# MCU.net
KiCad netlist of a schematic drawn in Altium Designer
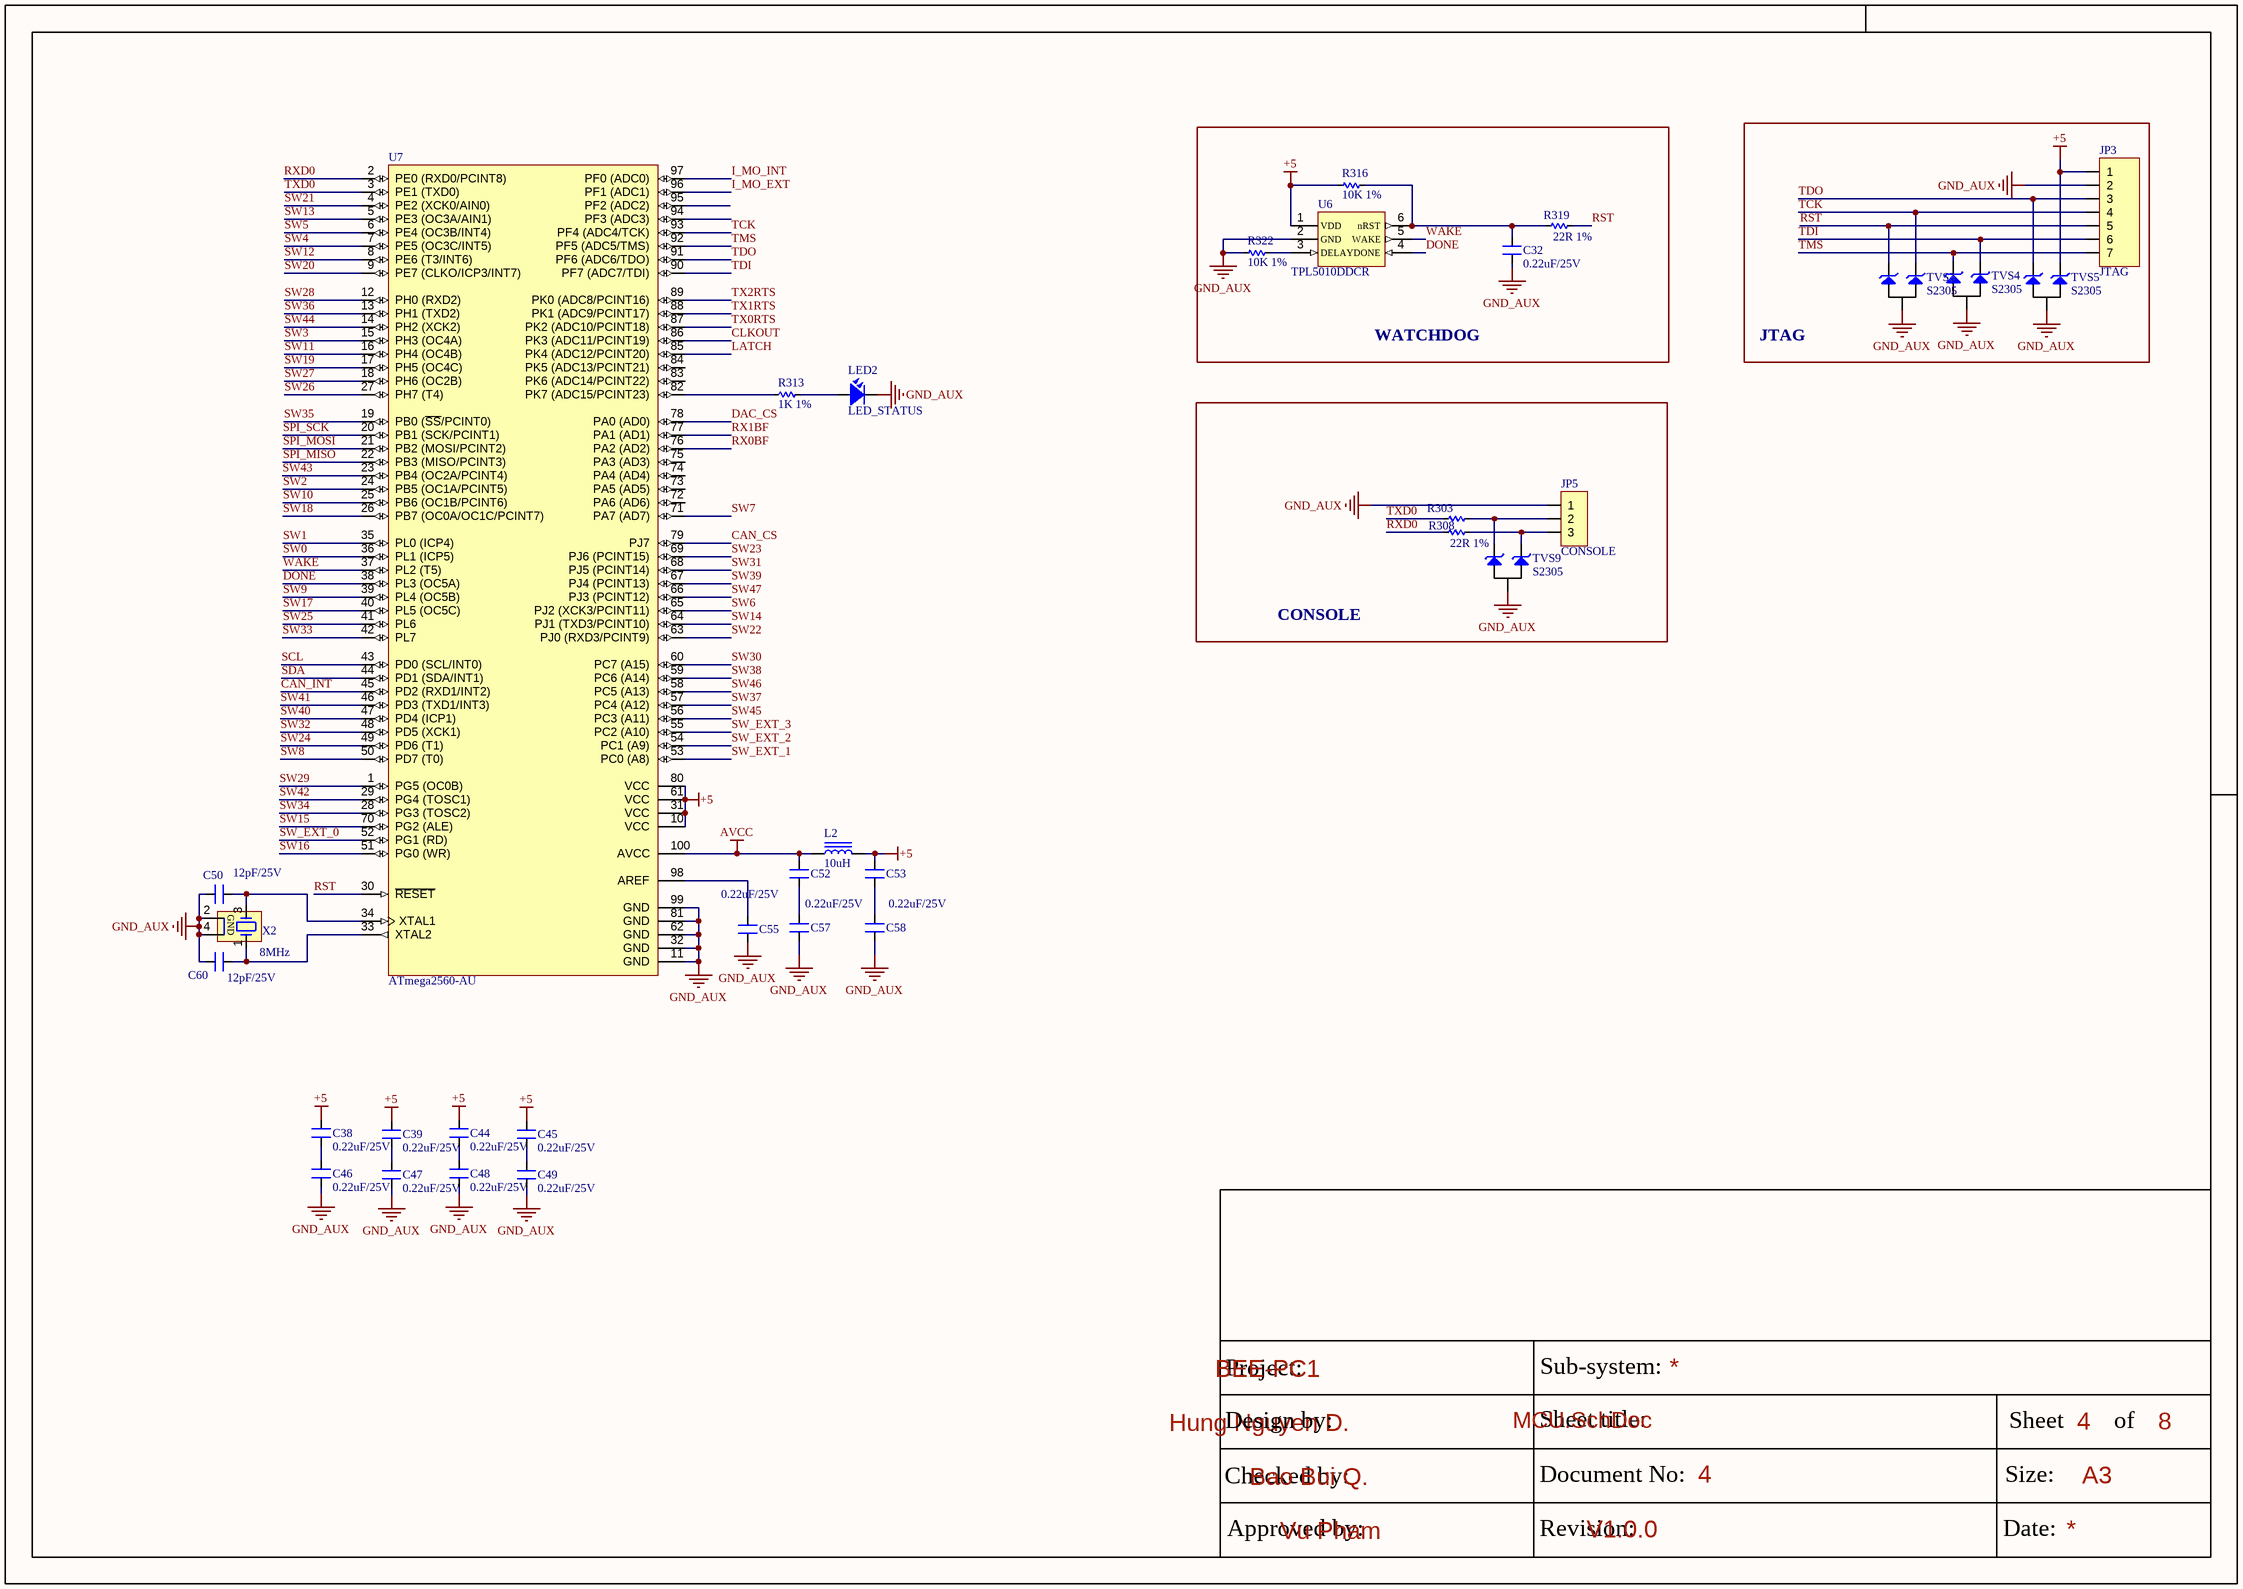
[diagram p0: MCU.SchDoc]

(export (version "E")
  (design (tool "Eeschema 10.0.6"))
  (components
    (comp (ref "C32")
      (value "0.22uF/25V")
      (footprint "SM-0603")
      (description "0603")
      (libsource (lib "Capacitors") (part "CM"))
    )
    (comp (ref "C38")
      (value "0.22uF/25V")
      (footprint "SM-0603")
      (description "0603")
      (libsource (lib "Capacitors") (part "CM"))
    )
    (comp (ref "C39")
      (value "0.22uF/25V")
      (footprint "SM-0603")
      (description "0603")
      (libsource (lib "Capacitors") (part "CM"))
    )
    (comp (ref "C44")
      (value "0.22uF/25V")
      (footprint "SM-0603")
      (description "0603")
      (libsource (lib "Capacitors") (part "CM"))
    )
    (comp (ref "C45")
      (value "0.22uF/25V")
      (footprint "SM-0603")
      (description "0603")
      (libsource (lib "Capacitors") (part "CM"))
    )
    (comp (ref "C46")
      (value "0.22uF/25V")
      (footprint "SM-0603")
      (description "0603")
      (libsource (lib "Capacitors") (part "CM"))
    )
    (comp (ref "C47")
      (value "0.22uF/25V")
      (footprint "SM-0603")
      (description "0603")
      (libsource (lib "Capacitors") (part "CM"))
    )
    (comp (ref "C48")
      (value "0.22uF/25V")
      (footprint "SM-0603")
      (description "0603")
      (libsource (lib "Capacitors") (part "CM"))
    )
    (comp (ref "C49")
      (value "0.22uF/25V")
      (footprint "SM-0603")
      (description "0603")
      (libsource (lib "Capacitors") (part "CM"))
    )
    (comp (ref "C50")
      (value "12pF/25V")
      (footprint "SM-0603")
      (description "0603")
      (libsource (lib "Capacitors") (part "CM"))
    )
    (comp (ref "C52")
      (value "0.22uF/25V")
      (footprint "SM-0603")
      (description "0603")
      (libsource (lib "Capacitors") (part "CM"))
    )
    (comp (ref "C53")
      (value "0.22uF/25V")
      (footprint "SM-0603")
      (description "0603")
      (libsource (lib "Capacitors") (part "CM"))
    )
    (comp (ref "C55")
      (value "0.22uF/25V")
      (footprint "SM-0603")
      (description "0603")
      (libsource (lib "Capacitors") (part "CM"))
    )
    (comp (ref "C57")
      (value "0.22uF/25V")
      (footprint "SM-0603")
      (description "0603")
      (libsource (lib "Capacitors") (part "CM"))
    )
    (comp (ref "C58")
      (value "0.22uF/25V")
      (footprint "SM-0603")
      (description "0603")
      (libsource (lib "Capacitors") (part "CM"))
    )
    (comp (ref "C60")
      (value "12pF/25V")
      (footprint "SM-0603")
      (description "0603")
      (libsource (lib "Capacitors") (part "CM"))
    )
    (comp (ref "JP3")
      (value "JTAG")
      (footprint "0532610771")
      (description "WR-PHD 2.54 mm Angled Socket Header")
      (fields
        (field (name "MANUFACTURER") "Würth Elektronik eiSos GmbH")
        (field (name "PARTNO") "613007143121")
        (field (name "CREATED BY") "Karrer Zheng")
      )
      (libsource (lib "Library") (part "JP7"))
    )
    (comp (ref "JP5")
      (value "CONSOLE")
      (footprint "0532610371")
      (description "WR-PHD 2.54 mm Angled Socket Header")
      (fields
        (field (name "MANUFACTURER") "Würth Elektronik eiSos GmbH")
        (field (name "PARTNO") "613003143121")
        (field (name "CREATED BY") "Karrer Zheng")
      )
      (libsource (lib "Library") (part "JP3"))
    )
    (comp (ref "L2")
      (value "10uH")
      (footprint "FER 0805/2012")
      (description "MLZ1608N100LT000")
      (libsource (lib "INDUCTOR") (part "Inductor"))
    )
    (comp (ref "LED2")
      (value "LED_STATUS")
      (footprint "GREENLED_0603")
      (libsource (lib "Library") (part "LED SMD"))
    )
    (comp (ref "R303")
      (value "22R 1%")
      (footprint "RES-SMD-0603")
      (description "0603")
      (fields
        (field (name "MANUFACTURER") "Generic Components")
        (field (name "PUBLISHER") "Altium Hobart Technology Centre")
      )
      (libsource (lib "Library") (part "Res-SMD"))
    )
    (comp (ref "R308")
      (value "22R 1%")
      (footprint "RES-SMD-0603")
      (description "0603")
      (fields
        (field (name "MANUFACTURER") "Generic Components")
        (field (name "PUBLISHER") "Altium Hobart Technology Centre")
      )
      (libsource (lib "Library") (part "Res-SMD"))
    )
    (comp (ref "R313")
      (value "1K 1%")
      (footprint "RES-SMD-0603")
      (description "0603")
      (fields
        (field (name "MANUFACTURER") "Generic Components")
        (field (name "PUBLISHER") "Altium Hobart Technology Centre")
      )
      (libsource (lib "Library") (part "Res-SMD"))
    )
    (comp (ref "R316")
      (value "10K 1%")
      (footprint "RES-SMD-0603")
      (description "0603")
      (fields
        (field (name "MANUFACTURER") "Generic Components")
        (field (name "PUBLISHER") "Altium Hobart Technology Centre")
      )
      (libsource (lib "Library") (part "Res-SMD"))
    )
    (comp (ref "R319")
      (value "22R 1%")
      (footprint "RES-SMD-0603")
      (description "0603")
      (fields
        (field (name "MANUFACTURER") "Generic Components")
        (field (name "PUBLISHER") "Altium Hobart Technology Centre")
      )
      (libsource (lib "Library") (part "Res-SMD"))
    )
    (comp (ref "R322")
      (value "10K 1%")
      (footprint "RES-SMD-0603")
      (description "0603")
      (fields
        (field (name "MANUFACTURER") "Generic Components")
        (field (name "PUBLISHER") "Altium Hobart Technology Centre")
      )
      (libsource (lib "Library") (part "Res-SMD"))
    )
    (comp (ref "TVS3")
      (value "S2305")
      (footprint "SOT23-123")
      (description "TVS DIODE 5VWM 10.8VC SOT23, P/N:  \r\nS2305")
      (libsource (lib "Library") (part "S2303"))
    )
    (comp (ref "TVS4")
      (value "S2305")
      (footprint "SOT23-123")
      (description "TVS DIODE 5VWM 10.8VC SOT23, P/N:  \r\nS2305")
      (libsource (lib "Library") (part "S2303"))
    )
    (comp (ref "TVS5")
      (value "S2305")
      (footprint "SOT23-123")
      (description "TVS DIODE 5VWM 10.8VC SOT23, P/N:  \r\nS2305")
      (libsource (lib "Library") (part "S2303"))
    )
    (comp (ref "TVS9")
      (value "S2305")
      (footprint "SOT23-123")
      (description "TVS DIODE 5VWM 10.8VC SOT23, P/N:  \r\nS2305")
      (libsource (lib "Library") (part "S2303"))
    )
    (comp (ref "U6")
      (value "TPL5010DDCR")
      (footprint "SOT23-6")
      (description "TSOT23-6")
      (libsource (lib "Library") (part "TPL5010DDCR"))
    )
    (comp (ref "U7")
      (value "ATmega2560-AU")
      (footprint "TQFP100L")
      (libsource (lib "Library") (part "ATmega2560-AU"))
    )
    (comp (ref "X2")
      (value "8MHz")
      (footprint "XT4-16.000MHz-4_V")
      (description "ECS-80-8-33Q-ADS")
      (libsource (lib "Library") (part "XT4"))
    )
  )
  (nets
    (net (code "1") (name "+5") (class "Default")
      (node (ref "C38") (pin "1") (pinfunction "1_1") (pintype "passive"))
      (node (ref "C39") (pin "1") (pinfunction "1_1") (pintype "passive"))
      (node (ref "C44") (pin "1") (pinfunction "1_1") (pintype "passive"))
      (node (ref "C45") (pin "1") (pinfunction "1_1") (pintype "passive"))
      (node (ref "C53") (pin "2") (pinfunction "2_2") (pintype "passive"))
      (node (ref "JP3") (pin "1") (pinfunction "1_1") (pintype "passive"))
      (node (ref "L2") (pin "2") (pinfunction "2_2") (pintype "passive"))
      (node (ref "R316") (pin "1") (pinfunction "1_1") (pintype "passive"))
      (node (ref "TVS5") (pin "3") (pintype "passive"))
      (node (ref "U6") (pin "1") (pinfunction "VDD_1") (pintype "power_in"))
      (node (ref "U7") (pin "10") (pinfunction "VCC_10") (pintype "power_in"))
      (node (ref "U7") (pin "31") (pinfunction "VCC_31") (pintype "power_in"))
      (node (ref "U7") (pin "61") (pinfunction "VCC_61") (pintype "power_in"))
      (node (ref "U7") (pin "80") (pinfunction "VCC_80") (pintype "power_in"))
    )
    (net (code "2") (name "/CAN_CS") (class "Default")
      (node (ref "U7") (pin "79") (pinfunction "PJ7_79") (pintype "bidirectional"))
    )
    (net (code "3") (name "/CAN_INT") (class "Default")
      (node (ref "U7") (pin "45") (pinfunction "PD2_(RXD1/INT2)_45") (pintype "bidirectional"))
    )
    (net (code "4") (name "/CLKOUT") (class "Default")
      (node (ref "U7") (pin "86") (pinfunction "PK3_(ADC11/PCINT19)_86") (pintype "bidirectional"))
    )
    (net (code "5") (name "/DAC_CS") (class "Default")
      (node (ref "U7") (pin "78") (pinfunction "PA0_(AD0)_78") (pintype "bidirectional"))
    )
    (net (code "6") (name "/DONE") (class "Default")
      (node (ref "U6") (pin "4") (pinfunction "DONE_4") (pintype "input"))
      (node (ref "U7") (pin "38") (pinfunction "PL3_(OC5A)_38") (pintype "bidirectional"))
    )
    (net (code "7") (name "/I_MO_EXT") (class "Default")
      (node (ref "U7") (pin "96") (pinfunction "PF1_(ADC1)_96") (pintype "bidirectional"))
    )
    (net (code "8") (name "/I_MO_INT") (class "Default")
      (node (ref "U7") (pin "97") (pinfunction "PF0_(ADC0)_97") (pintype "bidirectional"))
    )
    (net (code "9") (name "/LATCH") (class "Default")
      (node (ref "U7") (pin "85") (pinfunction "PK4_(ADC12/PCINT20)_85") (pintype "bidirectional"))
    )
    (net (code "10") (name "/RST") (class "Default")
      (node (ref "JP3") (pin "5") (pinfunction "5_5") (pintype "passive"))
      (node (ref "R319") (pin "2") (pinfunction "2_2") (pintype "passive"))
      (node (ref "TVS3") (pin "1") (pintype "passive"))
      (node (ref "U7") (pin "30") (pinfunction "~{RESET}_30") (pintype "input"))
    )
    (net (code "11") (name "/RX0BF") (class "Default")
      (node (ref "U7") (pin "76") (pinfunction "PA2_(AD2)_76") (pintype "bidirectional"))
    )
    (net (code "12") (name "/RX1BF") (class "Default")
      (node (ref "U7") (pin "77") (pinfunction "PA1_(AD1)_77") (pintype "bidirectional"))
    )
    (net (code "13") (name "/RXD0") (class "Default")
      (node (ref "R308") (pin "1") (pinfunction "1_1") (pintype "passive"))
      (node (ref "U7") (pin "2") (pinfunction "PE0_(RXD0/PCINT8)_2") (pintype "bidirectional"))
    )
    (net (code "14") (name "/SCL") (class "Default")
      (node (ref "U7") (pin "43") (pinfunction "PD0_(SCL/INT0)_43") (pintype "bidirectional"))
    )
    (net (code "15") (name "/SDA") (class "Default")
      (node (ref "U7") (pin "44") (pinfunction "PD1_(SDA/INT1)_44") (pintype "bidirectional"))
    )
    (net (code "16") (name "/SPI_MISO") (class "Default")
      (node (ref "U7") (pin "22") (pinfunction "PB3_(MISO/PCINT3)_22") (pintype "bidirectional"))
    )
    (net (code "17") (name "/SPI_MOSI") (class "Default")
      (node (ref "U7") (pin "21") (pinfunction "PB2_(MOSI/PCINT2)_21") (pintype "bidirectional"))
    )
    (net (code "18") (name "/SPI_SCK") (class "Default")
      (node (ref "U7") (pin "20") (pinfunction "PB1_(SCK/PCINT1)_20") (pintype "bidirectional"))
    )
    (net (code "19") (name "/SW0") (class "Default")
      (node (ref "U7") (pin "36") (pinfunction "PL1_(ICP5)_36") (pintype "bidirectional"))
    )
    (net (code "20") (name "/SW1") (class "Default")
      (node (ref "U7") (pin "35") (pinfunction "PL0_(ICP4)_35") (pintype "bidirectional"))
    )
    (net (code "21") (name "/SW2") (class "Default")
      (node (ref "U7") (pin "24") (pinfunction "PB5_(OC1A/PCINT5)_24") (pintype "bidirectional"))
    )
    (net (code "22") (name "/SW3") (class "Default")
      (node (ref "U7") (pin "15") (pinfunction "PH3_(OC4A)_15") (pintype "bidirectional"))
    )
    (net (code "23") (name "/SW4") (class "Default")
      (node (ref "U7") (pin "7") (pinfunction "PE5_(OC3C/INT5)_7") (pintype "bidirectional"))
    )
    (net (code "24") (name "/SW5") (class "Default")
      (node (ref "U7") (pin "6") (pinfunction "PE4_(OC3B/INT4)_6") (pintype "bidirectional"))
    )
    (net (code "25") (name "/SW6") (class "Default")
      (node (ref "U7") (pin "65") (pinfunction "PJ2_(XCK3/PCINT11)_65") (pintype "bidirectional"))
    )
    (net (code "26") (name "/SW7") (class "Default")
      (node (ref "U7") (pin "71") (pinfunction "PA7_(AD7)_71") (pintype "bidirectional"))
    )
    (net (code "27") (name "/SW8") (class "Default")
      (node (ref "U7") (pin "50") (pinfunction "PD7_(T0)_50") (pintype "bidirectional"))
    )
    (net (code "28") (name "/SW9") (class "Default")
      (node (ref "U7") (pin "39") (pinfunction "PL4_(OC5B)_39") (pintype "bidirectional"))
    )
    (net (code "29") (name "/SW10") (class "Default")
      (node (ref "U7") (pin "25") (pinfunction "PB6_(OC1B/PCINT6)_25") (pintype "bidirectional"))
    )
    (net (code "30") (name "/SW11") (class "Default")
      (node (ref "U7") (pin "16") (pinfunction "PH4_(OC4B)_16") (pintype "bidirectional"))
    )
    (net (code "31") (name "/SW12") (class "Default")
      (node (ref "U7") (pin "8") (pinfunction "PE6_(T3/INT6)_8") (pintype "bidirectional"))
    )
    (net (code "32") (name "/SW13") (class "Default")
      (node (ref "U7") (pin "5") (pinfunction "PE3_(OC3A/AIN1)_5") (pintype "bidirectional"))
    )
    (net (code "33") (name "/SW14") (class "Default")
      (node (ref "U7") (pin "64") (pinfunction "PJ1_(TXD3/PCINT10)_64") (pintype "bidirectional"))
    )
    (net (code "34") (name "/SW15") (class "Default")
      (node (ref "U7") (pin "70") (pinfunction "PG2_(ALE)_70") (pintype "bidirectional"))
    )
    (net (code "35") (name "/SW16") (class "Default")
      (node (ref "U7") (pin "51") (pinfunction "PG0_(WR)_51") (pintype "bidirectional"))
    )
    (net (code "36") (name "/SW17") (class "Default")
      (node (ref "U7") (pin "40") (pinfunction "PL5_(OC5C)_40") (pintype "bidirectional"))
    )
    (net (code "37") (name "/SW18") (class "Default")
      (node (ref "U7") (pin "26") (pinfunction "PB7_(OC0A/OC1C/PCINT7)_26") (pintype "bidirectional"))
    )
    (net (code "38") (name "/SW19") (class "Default")
      (node (ref "U7") (pin "17") (pinfunction "PH5_(OC4C)_17") (pintype "bidirectional"))
    )
    (net (code "39") (name "/SW20") (class "Default")
      (node (ref "U7") (pin "9") (pinfunction "PE7_(CLKO/ICP3/INT7)_9") (pintype "bidirectional"))
    )
    (net (code "40") (name "/SW21") (class "Default")
      (node (ref "U7") (pin "4") (pinfunction "PE2_(XCK0/AIN0)_4") (pintype "bidirectional"))
    )
    (net (code "41") (name "/SW22") (class "Default")
      (node (ref "U7") (pin "63") (pinfunction "PJ0_(RXD3/PCINT9)_63") (pintype "bidirectional"))
    )
    (net (code "42") (name "/SW23") (class "Default")
      (node (ref "U7") (pin "69") (pinfunction "PJ6_(PCINT15)_69") (pintype "bidirectional"))
    )
    (net (code "43") (name "/SW24") (class "Default")
      (node (ref "U7") (pin "49") (pinfunction "PD6_(T1)_49") (pintype "bidirectional"))
    )
    (net (code "44") (name "/SW25") (class "Default")
      (node (ref "U7") (pin "41") (pinfunction "PL6_41") (pintype "bidirectional"))
    )
    (net (code "45") (name "/SW26") (class "Default")
      (node (ref "U7") (pin "27") (pinfunction "PH7_(T4)_27") (pintype "bidirectional"))
    )
    (net (code "46") (name "/SW27") (class "Default")
      (node (ref "U7") (pin "18") (pinfunction "PH6_(OC2B)_18") (pintype "bidirectional"))
    )
    (net (code "47") (name "/SW28") (class "Default")
      (node (ref "U7") (pin "12") (pinfunction "PH0_(RXD2)_12") (pintype "bidirectional"))
    )
    (net (code "48") (name "/SW29") (class "Default")
      (node (ref "U7") (pin "1") (pinfunction "PG5_(OC0B)_1") (pintype "bidirectional"))
    )
    (net (code "49") (name "/SW30") (class "Default")
      (node (ref "U7") (pin "60") (pinfunction "PC7_(A15)_60") (pintype "bidirectional"))
    )
    (net (code "50") (name "/SW31") (class "Default")
      (node (ref "U7") (pin "68") (pinfunction "PJ5_(PCINT14)_68") (pintype "bidirectional"))
    )
    (net (code "51") (name "/SW32") (class "Default")
      (node (ref "U7") (pin "48") (pinfunction "PD5_(XCK1)_48") (pintype "bidirectional"))
    )
    (net (code "52") (name "/SW33") (class "Default")
      (node (ref "U7") (pin "42") (pinfunction "PL7_42") (pintype "bidirectional"))
    )
    (net (code "53") (name "/SW34") (class "Default")
      (node (ref "U7") (pin "28") (pinfunction "PG3_(TOSC2)_28") (pintype "bidirectional"))
    )
    (net (code "54") (name "/SW35") (class "Default")
      (node (ref "U7") (pin "19") (pinfunction "PB0_(~{SS}/PCINT0)_19") (pintype "bidirectional"))
    )
    (net (code "55") (name "/SW36") (class "Default")
      (node (ref "U7") (pin "13") (pinfunction "PH1_(TXD2)_13") (pintype "bidirectional"))
    )
    (net (code "56") (name "/SW37") (class "Default")
      (node (ref "U7") (pin "57") (pinfunction "PC4_(A12)_57") (pintype "bidirectional"))
    )
    (net (code "57") (name "/SW38") (class "Default")
      (node (ref "U7") (pin "59") (pinfunction "PC6_(A14)_59") (pintype "bidirectional"))
    )
    (net (code "58") (name "/SW39") (class "Default")
      (node (ref "U7") (pin "67") (pinfunction "PJ4_(PCINT13)_67") (pintype "bidirectional"))
    )
    (net (code "59") (name "/SW40") (class "Default")
      (node (ref "U7") (pin "47") (pinfunction "PD4_(ICP1)_47") (pintype "bidirectional"))
    )
    (net (code "60") (name "/SW41") (class "Default")
      (node (ref "U7") (pin "46") (pinfunction "PD3_(TXD1/INT3)_46") (pintype "bidirectional"))
    )
    (net (code "61") (name "/SW42") (class "Default")
      (node (ref "U7") (pin "29") (pinfunction "PG4_(TOSC1)_29") (pintype "bidirectional"))
    )
    (net (code "62") (name "/SW43") (class "Default")
      (node (ref "U7") (pin "23") (pinfunction "PB4_(OC2A/PCINT4)_23") (pintype "bidirectional"))
    )
    (net (code "63") (name "/SW44") (class "Default")
      (node (ref "U7") (pin "14") (pinfunction "PH2_(XCK2)_14") (pintype "bidirectional"))
    )
    (net (code "64") (name "/SW45") (class "Default")
      (node (ref "U7") (pin "56") (pinfunction "PC3_(A11)_56") (pintype "bidirectional"))
    )
    (net (code "65") (name "/SW46") (class "Default")
      (node (ref "U7") (pin "58") (pinfunction "PC5_(A13)_58") (pintype "bidirectional"))
    )
    (net (code "66") (name "/SW47") (class "Default")
      (node (ref "U7") (pin "66") (pinfunction "PJ3_(PCINT12)_66") (pintype "bidirectional"))
    )
    (net (code "67") (name "/SW_EXT_0") (class "Default")
      (node (ref "U7") (pin "52") (pinfunction "PG1_(RD)_52") (pintype "bidirectional"))
    )
    (net (code "68") (name "/SW_EXT_1") (class "Default")
      (node (ref "U7") (pin "53") (pinfunction "PC0_(A8)_53") (pintype "bidirectional"))
    )
    (net (code "69") (name "/SW_EXT_2") (class "Default")
      (node (ref "U7") (pin "54") (pinfunction "PC1_(A9)_54") (pintype "bidirectional"))
    )
    (net (code "70") (name "/SW_EXT_3") (class "Default")
      (node (ref "U7") (pin "55") (pinfunction "PC2_(A10)_55") (pintype "bidirectional"))
    )
    (net (code "71") (name "/TCK") (class "Default")
      (node (ref "JP3") (pin "4") (pinfunction "4_4") (pintype "passive"))
      (node (ref "TVS3") (pin "3") (pintype "passive"))
      (node (ref "U7") (pin "93") (pinfunction "PF4_(ADC4/TCK)_93") (pintype "bidirectional"))
    )
    (net (code "72") (name "/TDI") (class "Default")
      (node (ref "JP3") (pin "6") (pinfunction "6_6") (pintype "passive"))
      (node (ref "TVS4") (pin "3") (pintype "passive"))
      (node (ref "U7") (pin "90") (pinfunction "PF7_(ADC7/TDI)_90") (pintype "bidirectional"))
    )
    (net (code "73") (name "/TDO") (class "Default")
      (node (ref "JP3") (pin "3") (pinfunction "3_3") (pintype "passive"))
      (node (ref "TVS5") (pin "1") (pintype "passive"))
      (node (ref "U7") (pin "91") (pinfunction "PF6_(ADC6/TDO)_91") (pintype "bidirectional"))
    )
    (net (code "74") (name "/TMS") (class "Default")
      (node (ref "JP3") (pin "7") (pinfunction "7_7") (pintype "passive"))
      (node (ref "TVS4") (pin "1") (pintype "passive"))
      (node (ref "U7") (pin "92") (pinfunction "PF5_(ADC5/TMS)_92") (pintype "bidirectional"))
    )
    (net (code "75") (name "/TX0RTS") (class "Default")
      (node (ref "U7") (pin "87") (pinfunction "PK2_(ADC10/PCINT18)_87") (pintype "bidirectional"))
    )
    (net (code "76") (name "/TX1RTS") (class "Default")
      (node (ref "U7") (pin "88") (pinfunction "PK1_(ADC9/PCINT17)_88") (pintype "bidirectional"))
    )
    (net (code "77") (name "/TX2RTS") (class "Default")
      (node (ref "U7") (pin "89") (pinfunction "PK0_(ADC8/PCINT16)_89") (pintype "bidirectional"))
    )
    (net (code "78") (name "/TXD0") (class "Default")
      (node (ref "R303") (pin "1") (pinfunction "1_1") (pintype "passive"))
      (node (ref "U7") (pin "3") (pinfunction "PE1_(TXD0)_3") (pintype "bidirectional"))
    )
    (net (code "79") (name "/WAKE") (class "Default")
      (node (ref "U6") (pin "5") (pinfunction "WAKE_5") (pintype "output"))
      (node (ref "U7") (pin "37") (pinfunction "PL2_(T5)_37") (pintype "bidirectional"))
    )
    (net (code "80") (name "AVCC") (class "Default")
      (node (ref "C52") (pin "2") (pinfunction "2_2") (pintype "passive"))
      (node (ref "L2") (pin "1") (pinfunction "1_1") (pintype "passive"))
      (node (ref "U7") (pin "100") (pinfunction "AVCC_100") (pintype "power_in"))
    )
    (net (code "81") (name "GND_AUX") (class "Default")
      (node (ref "C32") (pin "2") (pinfunction "2_2") (pintype "passive"))
      (node (ref "C46") (pin "2") (pinfunction "2_2") (pintype "passive"))
      (node (ref "C47") (pin "2") (pinfunction "2_2") (pintype "passive"))
      (node (ref "C48") (pin "2") (pinfunction "2_2") (pintype "passive"))
      (node (ref "C49") (pin "2") (pinfunction "2_2") (pintype "passive"))
      (node (ref "C50") (pin "2") (pinfunction "2_2") (pintype "passive"))
      (node (ref "C55") (pin "1") (pinfunction "1_1") (pintype "passive"))
      (node (ref "C57") (pin "1") (pinfunction "1_1") (pintype "passive"))
      (node (ref "C58") (pin "1") (pinfunction "1_1") (pintype "passive"))
      (node (ref "C60") (pin "2") (pinfunction "2_2") (pintype "passive"))
      (node (ref "JP3") (pin "2") (pinfunction "2_2") (pintype "passive"))
      (node (ref "JP5") (pin "1") (pinfunction "1_1") (pintype "passive"))
      (node (ref "LED2") (pin "2") (pinfunction "2_2") (pintype "passive"))
      (node (ref "R322") (pin "1") (pinfunction "1_1") (pintype "passive"))
      (node (ref "TVS3") (pin "2") (pintype "passive"))
      (node (ref "TVS4") (pin "2") (pintype "passive"))
      (node (ref "TVS5") (pin "2") (pintype "passive"))
      (node (ref "TVS9") (pin "2") (pintype "passive"))
      (node (ref "U6") (pin "2") (pinfunction "GND_2") (pintype "power_in"))
      (node (ref "U7") (pin "11") (pinfunction "GND_11") (pintype "power_in"))
      (node (ref "U7") (pin "32") (pinfunction "GND_32") (pintype "power_in"))
      (node (ref "U7") (pin "62") (pinfunction "GND_62") (pintype "power_in"))
      (node (ref "U7") (pin "81") (pinfunction "GND_81") (pintype "power_in"))
      (node (ref "U7") (pin "99") (pinfunction "GND_99") (pintype "power_in"))
      (node (ref "X2") (pin "2") (pinfunction "GND_2") (pintype "power_in"))
      (node (ref "X2") (pin "4") (pinfunction "GND_4") (pintype "power_in"))
    )
    (net (code "82") (name "Net-(C38-Pad2)") (class "Default")
      (node (ref "C38") (pin "2") (pinfunction "2_2") (pintype "passive"))
      (node (ref "C46") (pin "1") (pinfunction "1_1") (pintype "passive"))
    )
    (net (code "83") (name "Net-(C39-Pad2)") (class "Default")
      (node (ref "C39") (pin "2") (pinfunction "2_2") (pintype "passive"))
      (node (ref "C47") (pin "1") (pinfunction "1_1") (pintype "passive"))
    )
    (net (code "84") (name "Net-(C44-Pad2)") (class "Default")
      (node (ref "C44") (pin "2") (pinfunction "2_2") (pintype "passive"))
      (node (ref "C48") (pin "1") (pinfunction "1_1") (pintype "passive"))
    )
    (net (code "85") (name "Net-(C45-Pad2)") (class "Default")
      (node (ref "C45") (pin "2") (pinfunction "2_2") (pintype "passive"))
      (node (ref "C49") (pin "1") (pinfunction "1_1") (pintype "passive"))
    )
    (net (code "86") (name "Net-(C52-Pad1)") (class "Default")
      (node (ref "C52") (pin "1") (pinfunction "1_1") (pintype "passive"))
      (node (ref "C57") (pin "2") (pinfunction "2_2") (pintype "passive"))
    )
    (net (code "87") (name "Net-(C53-Pad1)") (class "Default")
      (node (ref "C53") (pin "1") (pinfunction "1_1") (pintype "passive"))
      (node (ref "C58") (pin "2") (pinfunction "2_2") (pintype "passive"))
    )
    (net (code "88") (name "Net-(JP5-Pad2)") (class "Default")
      (node (ref "JP5") (pin "2") (pinfunction "2_2") (pintype "passive"))
      (node (ref "R303") (pin "2") (pinfunction "2_2") (pintype "passive"))
      (node (ref "TVS9") (pin "1") (pintype "passive"))
    )
    (net (code "89") (name "Net-(JP5-Pad3)") (class "Default")
      (node (ref "JP5") (pin "3") (pinfunction "3_3") (pintype "passive"))
      (node (ref "R308") (pin "2") (pinfunction "2_2") (pintype "passive"))
      (node (ref "TVS9") (pin "3") (pintype "passive"))
    )
    (net (code "90") (name "Net-(LED2-Pad1)") (class "Default")
      (node (ref "LED2") (pin "1") (pinfunction "1_1") (pintype "passive"))
      (node (ref "R313") (pin "1") (pinfunction "1_1") (pintype "passive"))
    )
    (net (code "91") (name "Net-(U6-DELAY)") (class "Default")
      (node (ref "R322") (pin "2") (pinfunction "2_2") (pintype "passive"))
      (node (ref "U6") (pin "3") (pinfunction "DELAY_3") (pintype "input"))
    )
    (net (code "92") (name "Net-(U6-nRST)") (class "Default")
      (node (ref "C32") (pin "1") (pinfunction "1_1") (pintype "passive"))
      (node (ref "R316") (pin "2") (pinfunction "2_2") (pintype "passive"))
      (node (ref "R319") (pin "1") (pinfunction "1_1") (pintype "passive"))
      (node (ref "U6") (pin "6") (pinfunction "nRST_6") (pintype "output"))
    )
    (net (code "93") (name "Net-(U7-AREF)") (class "Default")
      (node (ref "C55") (pin "2") (pinfunction "2_2") (pintype "passive"))
      (node (ref "U7") (pin "98") (pinfunction "AREF_98") (pintype "power_in"))
    )
    (net (code "94") (name "Net-(U7-PK7_(ADC15{slash}PCINT23))") (class "Default")
      (node (ref "R313") (pin "2") (pinfunction "2_2") (pintype "passive"))
      (node (ref "U7") (pin "82") (pinfunction "PK7_(ADC15/PCINT23)_82") (pintype "bidirectional"))
    )
    (net (code "95") (name "Net-(U7-XTAL1)") (class "Default")
      (node (ref "C50") (pin "1") (pinfunction "1_1") (pintype "passive"))
      (node (ref "U7") (pin "34") (pinfunction "XTAL1_34") (pintype "input"))
      (node (ref "X2") (pin "3") (pinfunction "XTAL_3") (pintype "passive"))
    )
    (net (code "96") (name "Net-(U7-XTAL2)") (class "Default")
      (node (ref "C60") (pin "1") (pinfunction "1_1") (pintype "passive"))
      (node (ref "U7") (pin "33") (pinfunction "XTAL2_33") (pintype "output"))
      (node (ref "X2") (pin "1") (pinfunction "XTAL_1") (pintype "passive"))
    )
    (net (code "97") (name "unconnected-(U7-PA3_(AD3)-Pad75)") (class "Default")
      (node (ref "U7") (pin "75") (pinfunction "PA3_(AD3)_75") (pintype "bidirectional"))
    )
    (net (code "98") (name "unconnected-(U7-PA4_(AD4)-Pad74)") (class "Default")
      (node (ref "U7") (pin "74") (pinfunction "PA4_(AD4)_74") (pintype "bidirectional"))
    )
    (net (code "99") (name "unconnected-(U7-PA5_(AD5)-Pad73)") (class "Default")
      (node (ref "U7") (pin "73") (pinfunction "PA5_(AD5)_73") (pintype "bidirectional"))
    )
    (net (code "100") (name "unconnected-(U7-PA6_(AD6)-Pad72)") (class "Default")
      (node (ref "U7") (pin "72") (pinfunction "PA6_(AD6)_72") (pintype "bidirectional"))
    )
    (net (code "101") (name "unconnected-(U7-PF2_(ADC2)-Pad95)") (class "Default")
      (node (ref "U7") (pin "95") (pinfunction "PF2_(ADC2)_95") (pintype "bidirectional"))
    )
    (net (code "102") (name "unconnected-(U7-PF3_(ADC3)-Pad94)") (class "Default")
      (node (ref "U7") (pin "94") (pinfunction "PF3_(ADC3)_94") (pintype "bidirectional"))
    )
    (net (code "103") (name "unconnected-(U7-PK5_(ADC13{slash}PCINT21)-Pad84)") (class "Default")
      (node (ref "U7") (pin "84") (pinfunction "PK5_(ADC13/PCINT21)_84") (pintype "bidirectional"))
    )
    (net (code "104") (name "unconnected-(U7-PK6_(ADC14{slash}PCINT22)-Pad83)") (class "Default")
      (node (ref "U7") (pin "83") (pinfunction "PK6_(ADC14/PCINT22)_83") (pintype "bidirectional"))
    )
  )
)
